# string_lights_revA.net
KiCad netlist of a schematic drawn in EAGLE
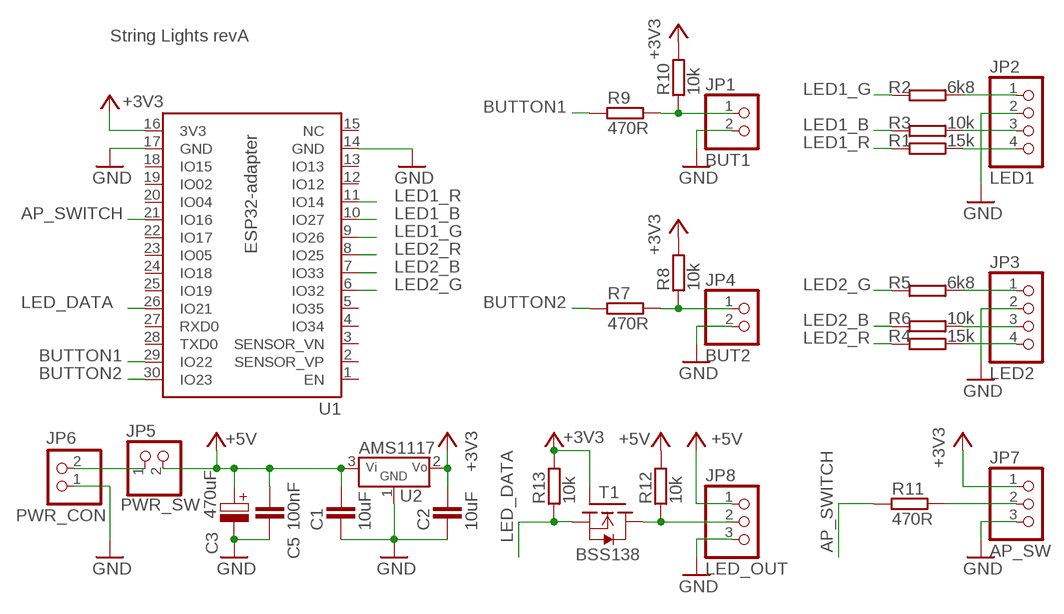
[diagram p0: schematic, sheet 1]

(export (version "E")
  (design (tool "Eeschema 10.0.6"))
  (components
    (comp (ref "C1")
      (value "10uF")
      (footprint "eagle-import:C0805")
      (libsource (lib "eagle-import") (part "C-CERAMIC'SMD'"))
    )
    (comp (ref "C2")
      (value "10uF")
      (footprint "eagle-import:C0805")
      (libsource (lib "eagle-import") (part "C-CERAMIC'SMD'"))
    )
    (comp (ref "C3")
      (value "470uF")
      (footprint "eagle-import:ELYT-10MM")
      (libsource (lib "eagle-import") (part "C-POLY'10MM'"))
    )
    (comp (ref "C5")
      (value "100nF")
      (footprint "eagle-import:C0805")
      (libsource (lib "eagle-import") (part "C-CERAMIC'SMD'"))
    )
    (comp (ref "JP1")
      (value "BUT1")
      (footprint "eagle-import:1X02_90")
      (libsource (lib "eagle-import") (part "PINHD-1X2/90"))
    )
    (comp (ref "JP2")
      (value "LED1")
      (footprint "eagle-import:1X04_90")
      (libsource (lib "eagle-import") (part "PINHD-1X4/90"))
    )
    (comp (ref "JP3")
      (value "LED2")
      (footprint "eagle-import:1X04_90")
      (libsource (lib "eagle-import") (part "PINHD-1X4/90"))
    )
    (comp (ref "JP4")
      (value "BUT2")
      (footprint "eagle-import:1X02_90")
      (libsource (lib "eagle-import") (part "PINHD-1X2/90"))
    )
    (comp (ref "JP5")
      (value "PWR_SW")
      (footprint "eagle-import:1X02_90")
      (libsource (lib "eagle-import") (part "PINHD-1X2/90"))
    )
    (comp (ref "JP6")
      (value "PWR_CON")
      (footprint "eagle-import:1X02_90")
      (libsource (lib "eagle-import") (part "PINHD-1X2/90"))
    )
    (comp (ref "JP7")
      (value "AP_SW")
      (footprint "eagle-import:1X03_90")
      (libsource (lib "eagle-import") (part "PINHD-1X3/90"))
    )
    (comp (ref "JP8")
      (value "LED_OUT")
      (footprint "eagle-import:1X03_90")
      (libsource (lib "eagle-import") (part "PINHD-1X3/90"))
    )
    (comp (ref "R1")
      (value "15k")
      (footprint "eagle-import:R0805")
      (libsource (lib "eagle-import") (part "R'2'"))
    )
    (comp (ref "R2")
      (value "6k8")
      (footprint "eagle-import:R0805")
      (libsource (lib "eagle-import") (part "R'2'"))
    )
    (comp (ref "R3")
      (value "10k")
      (footprint "eagle-import:R0805")
      (libsource (lib "eagle-import") (part "R'2'"))
    )
    (comp (ref "R4")
      (value "15k")
      (footprint "eagle-import:R0805")
      (libsource (lib "eagle-import") (part "R'2'"))
    )
    (comp (ref "R5")
      (value "6k8")
      (footprint "eagle-import:R0805")
      (libsource (lib "eagle-import") (part "R'2'"))
    )
    (comp (ref "R6")
      (value "10k")
      (footprint "eagle-import:R0805")
      (libsource (lib "eagle-import") (part "R'2'"))
    )
    (comp (ref "R7")
      (value "470R")
      (footprint "eagle-import:R0805")
      (libsource (lib "eagle-import") (part "R'2'"))
    )
    (comp (ref "R8")
      (value "10k")
      (footprint "eagle-import:R0805")
      (libsource (lib "eagle-import") (part "R'2'"))
    )
    (comp (ref "R9")
      (value "470R")
      (footprint "eagle-import:R0805")
      (libsource (lib "eagle-import") (part "R'2'"))
    )
    (comp (ref "R10")
      (value "10k")
      (footprint "eagle-import:R0805")
      (libsource (lib "eagle-import") (part "R'2'"))
    )
    (comp (ref "R11")
      (value "470R")
      (footprint "eagle-import:R0805")
      (libsource (lib "eagle-import") (part "R'2'"))
    )
    (comp (ref "R12")
      (value "10k")
      (footprint "eagle-import:R0805")
      (libsource (lib "eagle-import") (part "R'2'"))
    )
    (comp (ref "R13")
      (value "10k")
      (footprint "eagle-import:R0805")
      (libsource (lib "eagle-import") (part "R'2'"))
    )
    (comp (ref "T1")
      (value "BSS138")
      (footprint "eagle-import:SOT23")
      (libsource (lib "eagle-import") (part "BSS138"))
    )
    (comp (ref "U1")
      (value "ESP32-ADAPTER")
      (footprint "eagle-import:ESP32-ADAPTER")
      (libsource (lib "eagle-import") (part "ESP32-ADAPTER"))
    )
    (comp (ref "U2")
      (value "AMS1117")
      (footprint "eagle-import:SOT223")
      (libsource (lib "eagle-import") (part "V_STAB'TS1117'"))
    )
  )
  (nets
    (net (code "1") (name "+3V3") (class "Default")
      (node (ref "C2") (pin "2") (pinfunction "P$2_2") (pintype "bidirectional"))
      (node (ref "JP7") (pin "1") (pinfunction "1_1") (pintype "passive"))
      (node (ref "R10") (pin "2") (pinfunction "P$2_2") (pintype "bidirectional"))
      (node (ref "R13") (pin "2") (pinfunction "P$2_2") (pintype "bidirectional"))
      (node (ref "R8") (pin "2") (pinfunction "P$2_2") (pintype "bidirectional"))
      (node (ref "T1") (pin "1") (pinfunction "G_1") (pintype "passive"))
      (node (ref "U1") (pin "16") (pinfunction "3V3_16") (pintype "bidirectional"))
      (node (ref "U2") (pin "2") (pinfunction "VOUT_2") (pintype "power_in"))
    )
    (net (code "2") (name "+5V") (class "Default")
      (node (ref "C1") (pin "2") (pinfunction "P$2_2") (pintype "bidirectional"))
      (node (ref "C3") (pin "P") (pinfunction "POS_P") (pintype "bidirectional"))
      (node (ref "C5") (pin "2") (pinfunction "P$2_2") (pintype "bidirectional"))
      (node (ref "JP5") (pin "2") (pinfunction "2_2") (pintype "passive"))
      (node (ref "JP8") (pin "1") (pinfunction "1_1") (pintype "passive"))
      (node (ref "R12") (pin "2") (pinfunction "P$2_2") (pintype "bidirectional"))
      (node (ref "U2") (pin "3") (pinfunction "VIN_3") (pintype "power_in"))
    )
    (net (code "3") (name "/AP_SWITCH") (class "Default")
      (node (ref "R11") (pin "1") (pinfunction "P$1_1") (pintype "bidirectional"))
      (node (ref "U1") (pin "21") (pinfunction "IO16_21") (pintype "bidirectional"))
    )
    (net (code "4") (name "/BUTTON1") (class "Default")
      (node (ref "R9") (pin "1") (pinfunction "P$1_1") (pintype "bidirectional"))
      (node (ref "U1") (pin "29") (pinfunction "IO22_29") (pintype "bidirectional"))
    )
    (net (code "5") (name "/BUTTON2") (class "Default")
      (node (ref "R7") (pin "1") (pinfunction "P$1_1") (pintype "bidirectional"))
      (node (ref "U1") (pin "30") (pinfunction "IO23_30") (pintype "bidirectional"))
    )
    (net (code "6") (name "/LED1_B") (class "Default")
      (node (ref "R3") (pin "1") (pinfunction "P$1_1") (pintype "bidirectional"))
      (node (ref "U1") (pin "10") (pinfunction "IO27_10") (pintype "bidirectional"))
    )
    (net (code "7") (name "/LED1_G") (class "Default")
      (node (ref "R2") (pin "1") (pinfunction "P$1_1") (pintype "bidirectional"))
      (node (ref "U1") (pin "9") (pinfunction "IO26_9") (pintype "bidirectional"))
    )
    (net (code "8") (name "/LED1_R") (class "Default")
      (node (ref "R1") (pin "1") (pinfunction "P$1_1") (pintype "bidirectional"))
      (node (ref "U1") (pin "11") (pinfunction "IO14_11") (pintype "bidirectional"))
    )
    (net (code "9") (name "/LED2_B") (class "Default")
      (node (ref "R6") (pin "1") (pinfunction "P$1_1") (pintype "bidirectional"))
      (node (ref "U1") (pin "7") (pinfunction "IO33_7") (pintype "bidirectional"))
    )
    (net (code "10") (name "/LED2_G") (class "Default")
      (node (ref "R5") (pin "1") (pinfunction "P$1_1") (pintype "bidirectional"))
      (node (ref "U1") (pin "6") (pinfunction "IO32_6") (pintype "bidirectional"))
    )
    (net (code "11") (name "/LED2_R") (class "Default")
      (node (ref "R4") (pin "1") (pinfunction "P$1_1") (pintype "bidirectional"))
      (node (ref "U1") (pin "8") (pinfunction "IO25_8") (pintype "bidirectional"))
    )
    (net (code "12") (name "/LED_DATA") (class "Default")
      (node (ref "R13") (pin "1") (pinfunction "P$1_1") (pintype "bidirectional"))
      (node (ref "T1") (pin "2") (pinfunction "S_2") (pintype "passive"))
      (node (ref "U1") (pin "26") (pinfunction "IO21_26") (pintype "bidirectional"))
    )
    (net (code "13") (name "GND") (class "Default")
      (node (ref "C1") (pin "1") (pinfunction "P$1_1") (pintype "bidirectional"))
      (node (ref "C2") (pin "1") (pinfunction "P$1_1") (pintype "bidirectional"))
      (node (ref "C3") (pin "N") (pinfunction "NEG_N") (pintype "bidirectional"))
      (node (ref "C5") (pin "1") (pinfunction "P$1_1") (pintype "bidirectional"))
      (node (ref "JP1") (pin "2") (pinfunction "2_2") (pintype "passive"))
      (node (ref "JP2") (pin "2") (pinfunction "2_2") (pintype "passive"))
      (node (ref "JP3") (pin "2") (pinfunction "2_2") (pintype "passive"))
      (node (ref "JP4") (pin "2") (pinfunction "2_2") (pintype "passive"))
      (node (ref "JP6") (pin "1") (pinfunction "1_1") (pintype "passive"))
      (node (ref "JP7") (pin "3") (pinfunction "3_3") (pintype "passive"))
      (node (ref "JP8") (pin "3") (pinfunction "3_3") (pintype "passive"))
      (node (ref "U1") (pin "14") (pinfunction "GND_14") (pintype "bidirectional"))
      (node (ref "U1") (pin "17") (pinfunction "GND_17") (pintype "bidirectional"))
      (node (ref "U2") (pin "1") (pinfunction "GND_1") (pintype "power_in"))
    )
    (net (code "14") (name "Net-(JP5-Pad1)") (class "Default")
      (node (ref "JP5") (pin "1") (pinfunction "1_1") (pintype "passive"))
      (node (ref "JP6") (pin "2") (pinfunction "2_2") (pintype "passive"))
    )
    (net (code "15") (name "Net-(R1-P$2)") (class "Default")
      (node (ref "JP2") (pin "4") (pinfunction "4_4") (pintype "passive"))
      (node (ref "R1") (pin "2") (pinfunction "P$2_2") (pintype "bidirectional"))
    )
    (net (code "16") (name "Net-(R2-P$2)") (class "Default")
      (node (ref "JP2") (pin "1") (pinfunction "1_1") (pintype "passive"))
      (node (ref "R2") (pin "2") (pinfunction "P$2_2") (pintype "bidirectional"))
    )
    (net (code "17") (name "Net-(R3-P$2)") (class "Default")
      (node (ref "JP2") (pin "3") (pinfunction "3_3") (pintype "passive"))
      (node (ref "R3") (pin "2") (pinfunction "P$2_2") (pintype "bidirectional"))
    )
    (net (code "18") (name "Net-(R4-P$2)") (class "Default")
      (node (ref "JP3") (pin "4") (pinfunction "4_4") (pintype "passive"))
      (node (ref "R4") (pin "2") (pinfunction "P$2_2") (pintype "bidirectional"))
    )
    (net (code "19") (name "Net-(R5-P$2)") (class "Default")
      (node (ref "JP3") (pin "1") (pinfunction "1_1") (pintype "passive"))
      (node (ref "R5") (pin "2") (pinfunction "P$2_2") (pintype "bidirectional"))
    )
    (net (code "20") (name "Net-(R6-P$2)") (class "Default")
      (node (ref "JP3") (pin "3") (pinfunction "3_3") (pintype "passive"))
      (node (ref "R6") (pin "2") (pinfunction "P$2_2") (pintype "bidirectional"))
    )
    (net (code "21") (name "Net-(R7-P$2)") (class "Default")
      (node (ref "JP4") (pin "1") (pinfunction "1_1") (pintype "passive"))
      (node (ref "R7") (pin "2") (pinfunction "P$2_2") (pintype "bidirectional"))
      (node (ref "R8") (pin "1") (pinfunction "P$1_1") (pintype "bidirectional"))
    )
    (net (code "22") (name "Net-(R10-P$1)") (class "Default")
      (node (ref "JP1") (pin "1") (pinfunction "1_1") (pintype "passive"))
      (node (ref "R10") (pin "1") (pinfunction "P$1_1") (pintype "bidirectional"))
      (node (ref "R9") (pin "2") (pinfunction "P$2_2") (pintype "bidirectional"))
    )
    (net (code "23") (name "Net-(R11-P$2)") (class "Default")
      (node (ref "JP7") (pin "2") (pinfunction "2_2") (pintype "passive"))
      (node (ref "R11") (pin "2") (pinfunction "P$2_2") (pintype "bidirectional"))
    )
    (net (code "24") (name "Net-(R12-P$1)") (class "Default")
      (node (ref "JP8") (pin "2") (pinfunction "2_2") (pintype "passive"))
      (node (ref "R12") (pin "1") (pinfunction "P$1_1") (pintype "bidirectional"))
      (node (ref "T1") (pin "3") (pinfunction "D_3") (pintype "passive"))
    )
    (net (code "25") (name "unconnected-(U1-EN-Pad1)") (class "Default")
      (node (ref "U1") (pin "1") (pinfunction "EN_1") (pintype "bidirectional"))
    )
    (net (code "26") (name "unconnected-(U1-IO02-Pad19)") (class "Default")
      (node (ref "U1") (pin "19") (pinfunction "IO02_19") (pintype "bidirectional"))
    )
    (net (code "27") (name "unconnected-(U1-IO04-Pad20)") (class "Default")
      (node (ref "U1") (pin "20") (pinfunction "IO04_20") (pintype "bidirectional"))
    )
    (net (code "28") (name "unconnected-(U1-IO05-Pad23)") (class "Default")
      (node (ref "U1") (pin "23") (pinfunction "IO05_23") (pintype "bidirectional"))
    )
    (net (code "29") (name "unconnected-(U1-IO12-Pad12)") (class "Default")
      (node (ref "U1") (pin "12") (pinfunction "IO12_12") (pintype "bidirectional"))
    )
    (net (code "30") (name "unconnected-(U1-IO13-Pad13)") (class "Default")
      (node (ref "U1") (pin "13") (pinfunction "IO13_13") (pintype "bidirectional"))
    )
    (net (code "31") (name "unconnected-(U1-IO15-Pad18)") (class "Default")
      (node (ref "U1") (pin "18") (pinfunction "IO15_18") (pintype "bidirectional"))
    )
    (net (code "32") (name "unconnected-(U1-IO17-Pad22)") (class "Default")
      (node (ref "U1") (pin "22") (pinfunction "IO17_22") (pintype "bidirectional"))
    )
    (net (code "33") (name "unconnected-(U1-IO18-Pad24)") (class "Default")
      (node (ref "U1") (pin "24") (pinfunction "IO18_24") (pintype "bidirectional"))
    )
    (net (code "34") (name "unconnected-(U1-IO19-Pad25)") (class "Default")
      (node (ref "U1") (pin "25") (pinfunction "IO19_25") (pintype "bidirectional"))
    )
    (net (code "35") (name "unconnected-(U1-IO34-Pad4)") (class "Default")
      (node (ref "U1") (pin "4") (pinfunction "IO34_4") (pintype "input"))
    )
    (net (code "36") (name "unconnected-(U1-IO35-Pad5)") (class "Default")
      (node (ref "U1") (pin "5") (pinfunction "IO35_5") (pintype "input"))
    )
    (net (code "37") (name "unconnected-(U1-NC-Pad15)") (class "Default")
      (node (ref "U1") (pin "15") (pinfunction "NC_15") (pintype "bidirectional"))
    )
    (net (code "38") (name "unconnected-(U1-RXD0-Pad27)") (class "Default")
      (node (ref "U1") (pin "27") (pinfunction "RXD0_27") (pintype "bidirectional"))
    )
    (net (code "39") (name "unconnected-(U1-SENSOR_VN-Pad3)") (class "Default")
      (node (ref "U1") (pin "3") (pinfunction "SENSOR_VN_3") (pintype "input"))
    )
    (net (code "40") (name "unconnected-(U1-SENSOR_VP-Pad2)") (class "Default")
      (node (ref "U1") (pin "2") (pinfunction "SENSOR_VP_2") (pintype "input"))
    )
    (net (code "41") (name "unconnected-(U1-TXD0-Pad28)") (class "Default")
      (node (ref "U1") (pin "28") (pinfunction "TXD0_28") (pintype "bidirectional"))
    )
  )
)
